# ELEKTRA-BENCH_v0_1-20240103.net
KiCad netlist of a schematic drawn in EAGLE
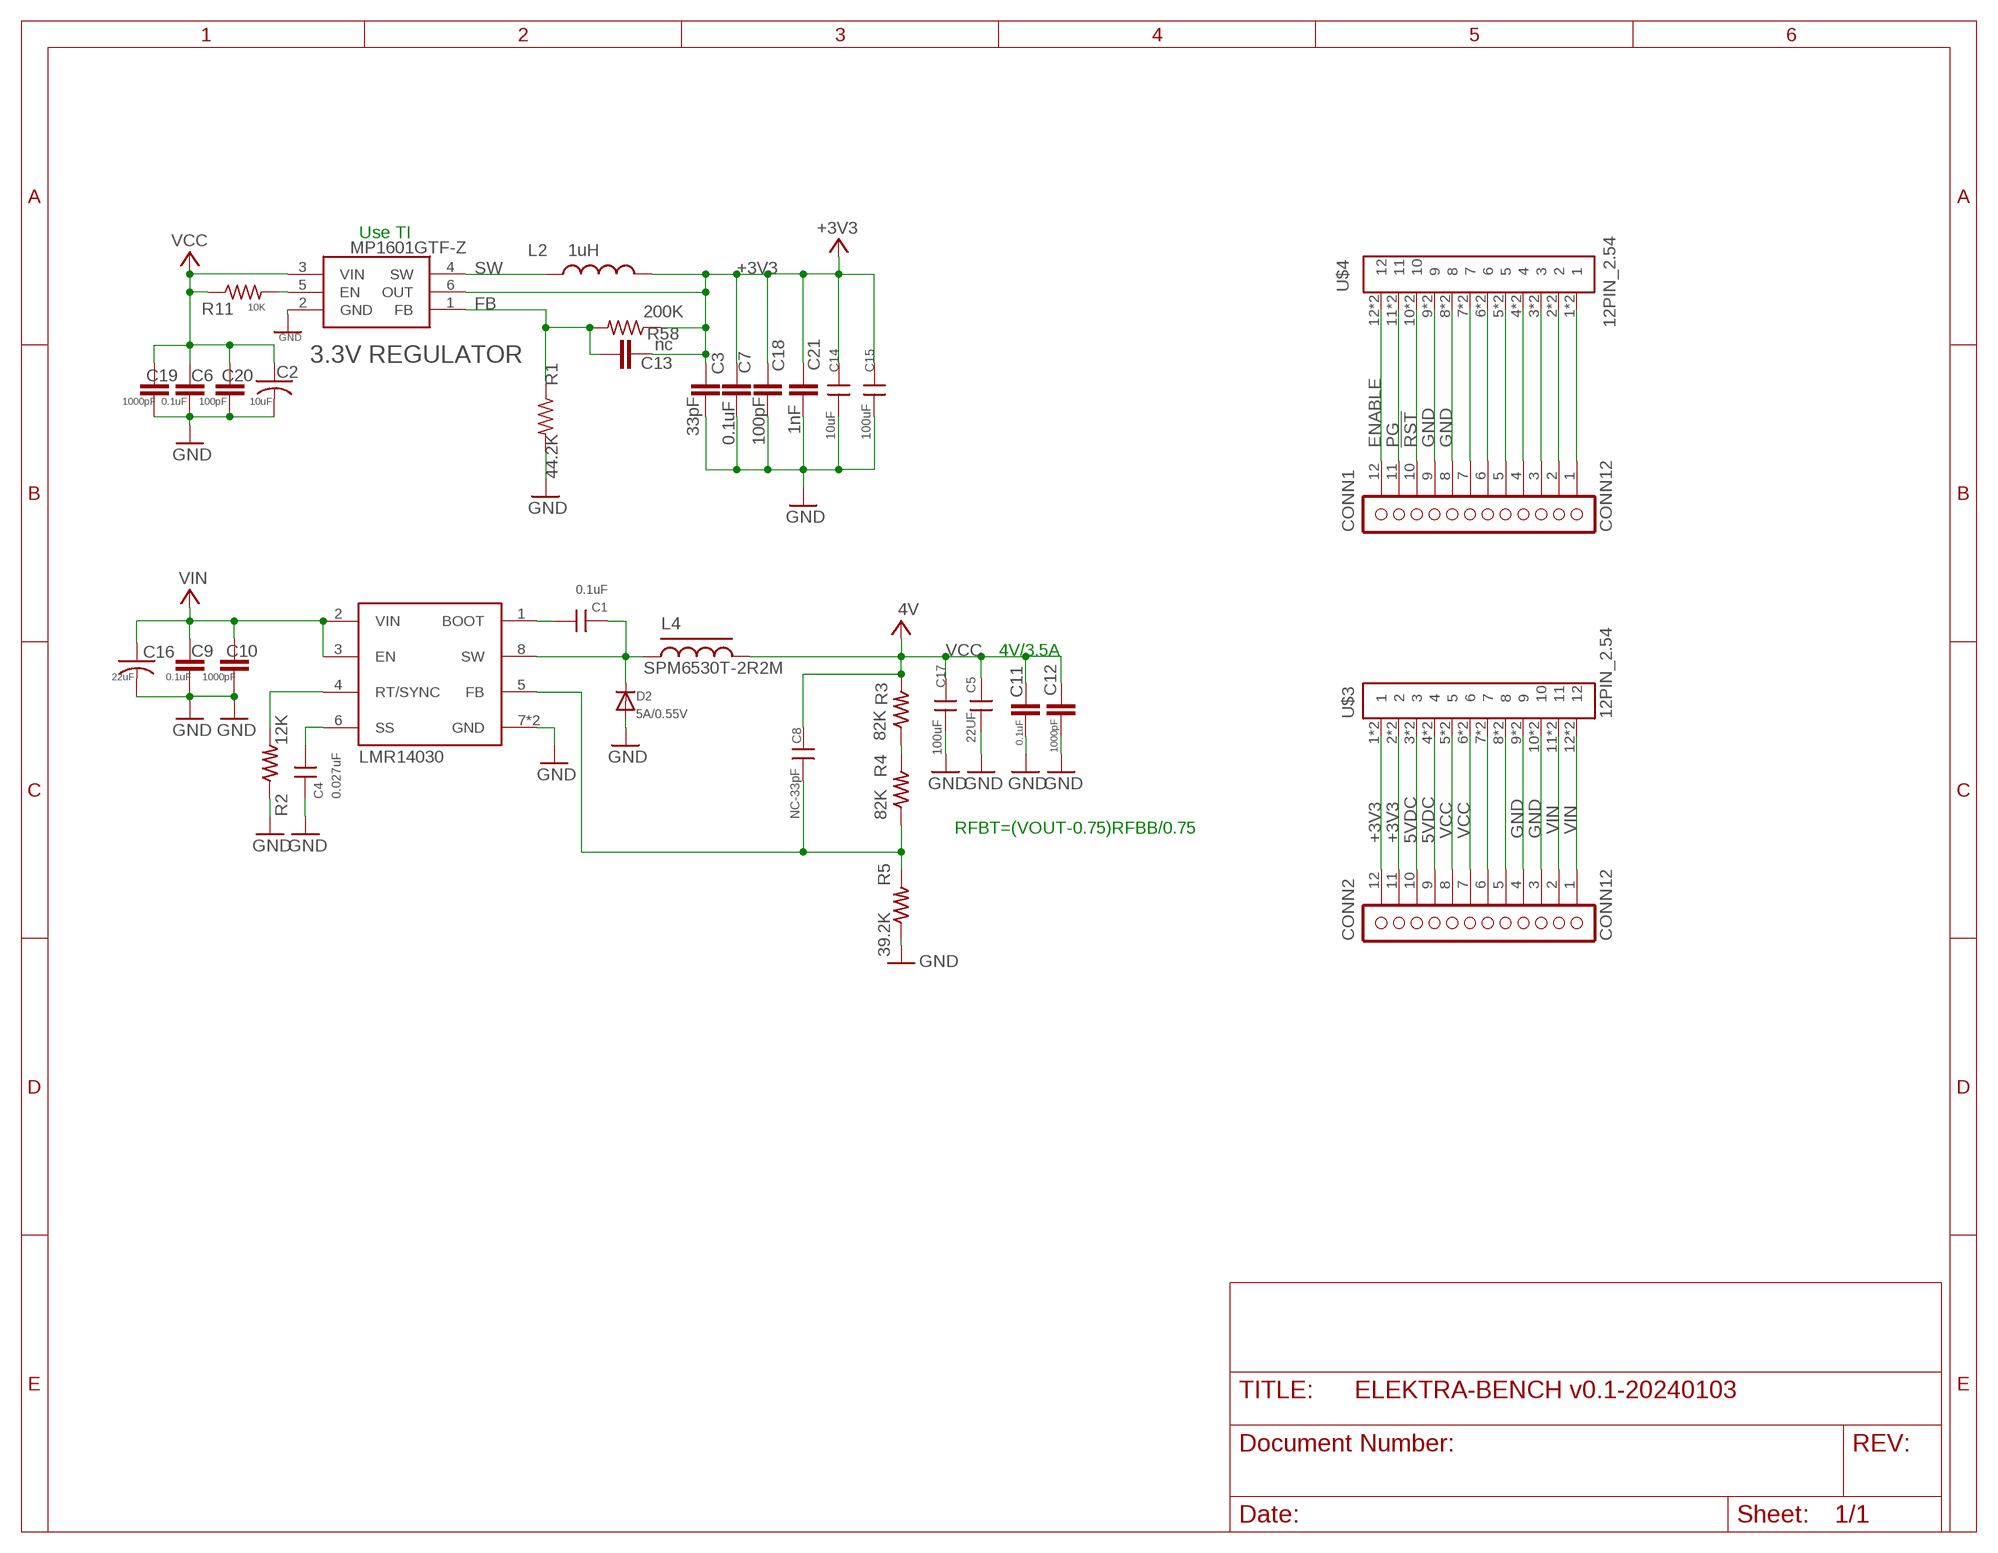
[diagram p0: schematic, sheet 1]

(export (version "E")
  (design (tool "Eeschema 10.0.6"))
  (components
    (comp (ref "C1")
      (value "0.1uF")
      (footprint "eagle-import:C0402")
      (libsource (lib "eagle-import") (part "particle SZ_21650216_CAP0402A"))
    )
    (comp (ref "C2")
      (value "10uF")
      (footprint "eagle-import:C0603_B")
      (libsource (lib "eagle-import") (part "C-US0603"))
    )
    (comp (ref "C3")
      (value "33pF")
      (footprint "eagle-import:C0402_B")
      (libsource (lib "eagle-import") (part "CAP_1"))
    )
    (comp (ref "C4")
      (value "0.027uF")
      (footprint "eagle-import:C0402")
      (libsource (lib "eagle-import") (part "particle SZ_21650216_CAP0402A"))
    )
    (comp (ref "C5")
      (value "22UF")
      (footprint "eagle-import:C0805")
      (libsource (lib "eagle-import") (part "CAPC0805"))
    )
    (comp (ref "C6")
      (value "0.1uF")
      (footprint "eagle-import:C0402_B")
      (libsource (lib "eagle-import") (part "CAP_1"))
    )
    (comp (ref "C7")
      (value "0.1uF")
      (footprint "eagle-import:C0402_B")
      (libsource (lib "eagle-import") (part "CAP_1"))
    )
    (comp (ref "C8")
      (value "NC-33pF")
      (footprint "eagle-import:C0402")
      (libsource (lib "eagle-import") (part "particle SZ_21650216_CAP0402A"))
    )
    (comp (ref "C9")
      (value "0.1uF")
      (footprint "eagle-import:C0402_B")
      (libsource (lib "eagle-import") (part "CAP_1"))
    )
    (comp (ref "C10")
      (value "1000pF")
      (footprint "eagle-import:C0402_B")
      (libsource (lib "eagle-import") (part "CAP_1"))
    )
    (comp (ref "C11")
      (value "0.1uF")
      (footprint "eagle-import:C0402_B")
      (libsource (lib "eagle-import") (part "CAP_1"))
    )
    (comp (ref "C12")
      (value "1000pF")
      (footprint "eagle-import:C0402_B")
      (libsource (lib "eagle-import") (part "CAP_1"))
    )
    (comp (ref "C13")
      (value "nc")
      (footprint "eagle-import:C0402_B")
      (libsource (lib "eagle-import") (part "CAP_1"))
    )
    (comp (ref "C14")
      (value "10uF")
      (footprint "eagle-import:C0805")
      (libsource (lib "eagle-import") (part "CAPC0805"))
    )
    (comp (ref "C15")
      (value "100uF")
      (footprint "eagle-import:C1206")
      (libsource (lib "eagle-import") (part "CAPC1206"))
    )
    (comp (ref "C16")
      (value "22uF")
      (footprint "eagle-import:C0603_B")
      (libsource (lib "eagle-import") (part "C-US0603"))
    )
    (comp (ref "C17")
      (value "100uF")
      (footprint "eagle-import:C1206")
      (libsource (lib "eagle-import") (part "CAPC1206"))
    )
    (comp (ref "C18")
      (value "100pF")
      (footprint "eagle-import:C0402_B")
      (libsource (lib "eagle-import") (part "CAP_1"))
    )
    (comp (ref "C19")
      (value "1000pF")
      (footprint "eagle-import:C0402_B")
      (libsource (lib "eagle-import") (part "CAP_1"))
    )
    (comp (ref "C20")
      (value "100pF")
      (footprint "eagle-import:C0402_B")
      (libsource (lib "eagle-import") (part "CAP_1"))
    )
    (comp (ref "C21")
      (value "1nF")
      (footprint "eagle-import:C0402_B")
      (libsource (lib "eagle-import") (part "CAP_1"))
    )
    (comp (ref "CONN1")
      (value "CONN12")
      (footprint "eagle-import:1X12_SMD_STRAIGHT")
      (libsource (lib "eagle-import") (part "CONN12"))
    )
    (comp (ref "CONN2")
      (value "CONN12")
      (footprint "eagle-import:1X12_SMD_STRAIGHT")
      (libsource (lib "eagle-import") (part "CONN12"))
    )
    (comp (ref "D2")
      (value "5A/0.55V")
      (footprint "eagle-import:SMADIODE")
      (libsource (lib "eagle-import") (part "DIODESMA"))
    )
    (comp (ref "L2")
      (value "1uH")
      (footprint "eagle-import:INDUCTOR-VLS-E")
      (libsource (lib "eagle-import") (part "INDUCTOR-SPARKFUNVLS3012ET-4R7M"))
    )
    (comp (ref "L4")
      (value "SPM6530T-2R2M")
      (footprint "eagle-import:INDCUTOR_SPM6530")
      (libsource (lib "eagle-import") (part "INDUCTOR"))
    )
    (comp (ref "R1")
      (value "44.2K")
      (footprint "eagle-import:R0402_B")
      (libsource (lib "eagle-import") (part "R-US_"))
    )
    (comp (ref "R2")
      (value "12K")
      (footprint "eagle-import:R-0402S")
      (libsource (lib "eagle-import") (part "RES0402S"))
    )
    (comp (ref "R3")
      (value "82K")
      (footprint "eagle-import:R-0402S")
      (libsource (lib "eagle-import") (part "RES0402S"))
    )
    (comp (ref "R4")
      (value "82K")
      (footprint "eagle-import:R-0402S")
      (libsource (lib "eagle-import") (part "RES0402S"))
    )
    (comp (ref "R5")
      (value "39.2K")
      (footprint "eagle-import:R-0402S")
      (libsource (lib "eagle-import") (part "RES0402S"))
    )
    (comp (ref "R11")
      (value "10K")
      (footprint "eagle-import:R0402_B")
      (libsource (lib "eagle-import") (part "Spark_R-US_"))
    )
    (comp (ref "R58")
      (value "200K")
      (footprint "eagle-import:R0402_B")
      (libsource (lib "eagle-import") (part "R-US_"))
    )
    (comp (ref "U$3")
      (value "12PIN_2.54")
      (footprint "eagle-import:12PIN_2.54")
      (libsource (lib "eagle-import") (part "12PIN_2.54"))
    )
    (comp (ref "U$4")
      (value "12PIN_2.54")
      (footprint "eagle-import:12PIN_2.54")
      (libsource (lib "eagle-import") (part "12PIN_2.54"))
    )
    (comp (ref "U2")
      (value "LMR14030")
      (footprint "eagle-import:SO_POWERPAD_8")
      (libsource (lib "eagle-import") (part "LMR14030"))
    )
    (comp (ref "U3")
      (value "MP1601GTF-Z")
      (footprint "eagle-import:SOTFL50P160X60-6N")
      (libsource (lib "eagle-import") (part "MP1601GTF-Z"))
    )
  )
  (nets
    (net (code "1") (name "+3V3") (class "Default")
      (node (ref "C13") (pin "1") (pinfunction "P$1_1") (pintype "passive"))
      (node (ref "C14") (pin "1") (pinfunction "1_1") (pintype "bidirectional"))
      (node (ref "C15") (pin "1") (pinfunction "1_1") (pintype "bidirectional"))
      (node (ref "C18") (pin "2") (pinfunction "P$2_2") (pintype "passive"))
      (node (ref "C21") (pin "2") (pinfunction "P$2_2") (pintype "passive"))
      (node (ref "C3") (pin "2") (pinfunction "P$2_2") (pintype "passive"))
      (node (ref "C7") (pin "2") (pinfunction "P$2_2") (pintype "passive"))
      (node (ref "CONN2") (pin "11") (pinfunction "11_11") (pintype "passive"))
      (node (ref "CONN2") (pin "12") (pinfunction "12_12") (pintype "passive"))
      (node (ref "L2") (pin "P$2") (pinfunction "2_P$2") (pintype "passive"))
      (node (ref "R58") (pin "1") (pinfunction "1_1") (pintype "passive"))
      (node (ref "U$3") (pin "1") (pinfunction "1_1") (pintype "bidirectional"))
      (node (ref "U$3") (pin "2") (pinfunction "2_2") (pintype "bidirectional"))
      (node (ref "U$3") (pin "P$1") (pinfunction "1_P$1") (pintype "bidirectional"))
      (node (ref "U$3") (pin "P$2") (pinfunction "2_P$2") (pintype "bidirectional"))
      (node (ref "U3") (pin "6") (pinfunction "OUT_6") (pintype "bidirectional"))
    )
    (net (code "2") (name "/5VDC") (class "Default")
      (node (ref "CONN2") (pin "10") (pinfunction "10_10") (pintype "passive"))
      (node (ref "CONN2") (pin "9") (pinfunction "9_9") (pintype "passive"))
      (node (ref "U$3") (pin "3") (pinfunction "3_3") (pintype "bidirectional"))
      (node (ref "U$3") (pin "4") (pinfunction "4_4") (pintype "bidirectional"))
      (node (ref "U$3") (pin "P$3") (pinfunction "3_P$3") (pintype "bidirectional"))
      (node (ref "U$3") (pin "P$4") (pinfunction "4_P$4") (pintype "bidirectional"))
    )
    (net (code "3") (name "/ENABLE") (class "Default")
      (node (ref "CONN1") (pin "12") (pinfunction "12_12") (pintype "passive"))
      (node (ref "U$4") (pin "12") (pinfunction "12_12") (pintype "bidirectional"))
      (node (ref "U$4") (pin "P$12") (pinfunction "12_P$12") (pintype "bidirectional"))
    )
    (net (code "4") (name "/FB") (class "Default")
      (node (ref "C13") (pin "2") (pinfunction "P$2_2") (pintype "passive"))
      (node (ref "R1") (pin "1") (pinfunction "1_1") (pintype "passive"))
      (node (ref "R58") (pin "2") (pinfunction "2_2") (pintype "passive"))
      (node (ref "U3") (pin "1") (pinfunction "FB_1") (pintype "bidirectional"))
    )
    (net (code "5") (name "/PG") (class "Default")
      (node (ref "CONN1") (pin "11") (pinfunction "11_11") (pintype "passive"))
      (node (ref "U$4") (pin "11") (pinfunction "11_11") (pintype "bidirectional"))
      (node (ref "U$4") (pin "P$11") (pinfunction "11_P$11") (pintype "bidirectional"))
    )
    (net (code "6") (name "/SW") (class "Default")
      (node (ref "L2") (pin "P$1") (pinfunction "1_P$1") (pintype "passive"))
      (node (ref "U3") (pin "4") (pinfunction "SW_4") (pintype "bidirectional"))
    )
    (net (code "7") (name "/~{RST}") (class "Default")
      (node (ref "CONN1") (pin "10") (pinfunction "10_10") (pintype "passive"))
      (node (ref "U$4") (pin "10") (pinfunction "10_10") (pintype "bidirectional"))
      (node (ref "U$4") (pin "P$10") (pinfunction "10_P$10") (pintype "bidirectional"))
    )
    (net (code "8") (name "4V") (class "Default")
      (node (ref "C11") (pin "2") (pinfunction "P$2_2") (pintype "passive"))
      (node (ref "C12") (pin "2") (pinfunction "P$2_2") (pintype "passive"))
      (node (ref "C17") (pin "1") (pinfunction "1_1") (pintype "bidirectional"))
      (node (ref "C19") (pin "2") (pinfunction "P$2_2") (pintype "passive"))
      (node (ref "C2") (pin "1") (pinfunction "1_1") (pintype "passive"))
      (node (ref "C20") (pin "2") (pinfunction "P$2_2") (pintype "passive"))
      (node (ref "C5") (pin "1") (pinfunction "1_1") (pintype "bidirectional"))
      (node (ref "C6") (pin "2") (pinfunction "P$2_2") (pintype "passive"))
      (node (ref "C8") (pin "2") (pinfunction "2_2") (pintype "bidirectional"))
      (node (ref "CONN2") (pin "7") (pinfunction "7_7") (pintype "passive"))
      (node (ref "CONN2") (pin "8") (pinfunction "8_8") (pintype "passive"))
      (node (ref "L4") (pin "2") (pinfunction "2_2") (pintype "bidirectional"))
      (node (ref "R11") (pin "1") (pinfunction "1_1") (pintype "passive"))
      (node (ref "R3") (pin "2") (pinfunction "2_2") (pintype "bidirectional"))
      (node (ref "U$3") (pin "5") (pinfunction "5_5") (pintype "bidirectional"))
      (node (ref "U$3") (pin "6") (pinfunction "6_6") (pintype "bidirectional"))
      (node (ref "U$3") (pin "P$5") (pinfunction "5_P$5") (pintype "bidirectional"))
      (node (ref "U$3") (pin "P$6") (pinfunction "6_P$6") (pintype "bidirectional"))
      (node (ref "U3") (pin "3") (pinfunction "VIN_3") (pintype "bidirectional"))
    )
    (net (code "9") (name "GND") (class "Default")
      (node (ref "C10") (pin "1") (pinfunction "P$1_1") (pintype "passive"))
      (node (ref "C11") (pin "1") (pinfunction "P$1_1") (pintype "passive"))
      (node (ref "C12") (pin "1") (pinfunction "P$1_1") (pintype "passive"))
      (node (ref "C14") (pin "2") (pinfunction "2_2") (pintype "bidirectional"))
      (node (ref "C15") (pin "2") (pinfunction "2_2") (pintype "bidirectional"))
      (node (ref "C16") (pin "2") (pinfunction "2_2") (pintype "passive"))
      (node (ref "C17") (pin "2") (pinfunction "2_2") (pintype "bidirectional"))
      (node (ref "C18") (pin "1") (pinfunction "P$1_1") (pintype "passive"))
      (node (ref "C19") (pin "1") (pinfunction "P$1_1") (pintype "passive"))
      (node (ref "C2") (pin "2") (pinfunction "2_2") (pintype "passive"))
      (node (ref "C20") (pin "1") (pinfunction "P$1_1") (pintype "passive"))
      (node (ref "C21") (pin "1") (pinfunction "P$1_1") (pintype "passive"))
      (node (ref "C3") (pin "1") (pinfunction "P$1_1") (pintype "passive"))
      (node (ref "C4") (pin "2") (pinfunction "2_2") (pintype "bidirectional"))
      (node (ref "C5") (pin "2") (pinfunction "2_2") (pintype "bidirectional"))
      (node (ref "C6") (pin "1") (pinfunction "P$1_1") (pintype "passive"))
      (node (ref "C7") (pin "1") (pinfunction "P$1_1") (pintype "passive"))
      (node (ref "C9") (pin "1") (pinfunction "P$1_1") (pintype "passive"))
      (node (ref "CONN1") (pin "8") (pinfunction "8_8") (pintype "passive"))
      (node (ref "CONN1") (pin "9") (pinfunction "9_9") (pintype "passive"))
      (node (ref "CONN2") (pin "3") (pinfunction "3_3") (pintype "passive"))
      (node (ref "CONN2") (pin "4") (pinfunction "4_4") (pintype "passive"))
      (node (ref "D2") (pin "A") (pinfunction "A_A") (pintype "passive"))
      (node (ref "R1") (pin "2") (pinfunction "2_2") (pintype "passive"))
      (node (ref "R2") (pin "1") (pinfunction "1_1") (pintype "bidirectional"))
      (node (ref "R5") (pin "1") (pinfunction "1_1") (pintype "bidirectional"))
      (node (ref "U$3") (pin "10") (pinfunction "10_10") (pintype "bidirectional"))
      (node (ref "U$3") (pin "9") (pinfunction "9_9") (pintype "bidirectional"))
      (node (ref "U$3") (pin "P$10") (pinfunction "10_P$10") (pintype "bidirectional"))
      (node (ref "U$3") (pin "P$9") (pinfunction "9_P$9") (pintype "bidirectional"))
      (node (ref "U$4") (pin "8") (pinfunction "8_8") (pintype "bidirectional"))
      (node (ref "U$4") (pin "9") (pinfunction "9_9") (pintype "bidirectional"))
      (node (ref "U$4") (pin "P$8") (pinfunction "8_P$8") (pintype "bidirectional"))
      (node (ref "U$4") (pin "P$9") (pinfunction "9_P$9") (pintype "bidirectional"))
      (node (ref "U2") (pin "7") (pinfunction "GND_7") (pintype "bidirectional"))
      (node (ref "U2") (pin "EP") (pinfunction "GND_EP") (pintype "bidirectional"))
      (node (ref "U3") (pin "2") (pinfunction "GND_2") (pintype "bidirectional"))
    )
    (net (code "10") (name "Net-(CONN1-Pad1)") (class "Default")
      (node (ref "CONN1") (pin "1") (pinfunction "1_1") (pintype "passive"))
      (node (ref "U$4") (pin "1") (pinfunction "1_1") (pintype "bidirectional"))
      (node (ref "U$4") (pin "P$1") (pinfunction "1_P$1") (pintype "bidirectional"))
    )
    (net (code "11") (name "Net-(CONN1-Pad2)") (class "Default")
      (node (ref "CONN1") (pin "2") (pinfunction "2_2") (pintype "passive"))
      (node (ref "U$4") (pin "2") (pinfunction "2_2") (pintype "bidirectional"))
      (node (ref "U$4") (pin "P$2") (pinfunction "2_P$2") (pintype "bidirectional"))
    )
    (net (code "12") (name "Net-(CONN1-Pad3)") (class "Default")
      (node (ref "CONN1") (pin "3") (pinfunction "3_3") (pintype "passive"))
      (node (ref "U$4") (pin "3") (pinfunction "3_3") (pintype "bidirectional"))
      (node (ref "U$4") (pin "P$3") (pinfunction "3_P$3") (pintype "bidirectional"))
    )
    (net (code "13") (name "Net-(CONN1-Pad4)") (class "Default")
      (node (ref "CONN1") (pin "4") (pinfunction "4_4") (pintype "passive"))
      (node (ref "U$4") (pin "4") (pinfunction "4_4") (pintype "bidirectional"))
      (node (ref "U$4") (pin "P$4") (pinfunction "4_P$4") (pintype "bidirectional"))
    )
    (net (code "14") (name "Net-(CONN1-Pad5)") (class "Default")
      (node (ref "CONN1") (pin "5") (pinfunction "5_5") (pintype "passive"))
      (node (ref "U$4") (pin "5") (pinfunction "5_5") (pintype "bidirectional"))
      (node (ref "U$4") (pin "P$5") (pinfunction "5_P$5") (pintype "bidirectional"))
    )
    (net (code "15") (name "Net-(CONN1-Pad6)") (class "Default")
      (node (ref "CONN1") (pin "6") (pinfunction "6_6") (pintype "passive"))
      (node (ref "U$4") (pin "6") (pinfunction "6_6") (pintype "bidirectional"))
      (node (ref "U$4") (pin "P$6") (pinfunction "6_P$6") (pintype "bidirectional"))
    )
    (net (code "16") (name "Net-(CONN1-Pad7)") (class "Default")
      (node (ref "CONN1") (pin "7") (pinfunction "7_7") (pintype "passive"))
      (node (ref "U$4") (pin "7") (pinfunction "7_7") (pintype "bidirectional"))
      (node (ref "U$4") (pin "P$7") (pinfunction "7_P$7") (pintype "bidirectional"))
    )
    (net (code "17") (name "Net-(CONN2-Pad5)") (class "Default")
      (node (ref "CONN2") (pin "5") (pinfunction "5_5") (pintype "passive"))
      (node (ref "U$3") (pin "8") (pinfunction "8_8") (pintype "bidirectional"))
      (node (ref "U$3") (pin "P$8") (pinfunction "8_P$8") (pintype "bidirectional"))
    )
    (net (code "18") (name "Net-(CONN2-Pad6)") (class "Default")
      (node (ref "CONN2") (pin "6") (pinfunction "6_6") (pintype "passive"))
      (node (ref "U$3") (pin "7") (pinfunction "7_7") (pintype "bidirectional"))
      (node (ref "U$3") (pin "P$7") (pinfunction "7_P$7") (pintype "bidirectional"))
    )
    (net (code "19") (name "Net-(R3-Pad1)") (class "Default")
      (node (ref "R3") (pin "1") (pinfunction "1_1") (pintype "bidirectional"))
      (node (ref "R4") (pin "2") (pinfunction "2_2") (pintype "bidirectional"))
    )
    (net (code "20") (name "Net-(U2-BOOT)") (class "Default")
      (node (ref "C1") (pin "1") (pinfunction "1_1") (pintype "bidirectional"))
      (node (ref "U2") (pin "1") (pinfunction "BOOT_1") (pintype "bidirectional"))
    )
    (net (code "21") (name "Net-(U2-FB)") (class "Default")
      (node (ref "C8") (pin "1") (pinfunction "1_1") (pintype "bidirectional"))
      (node (ref "R4") (pin "1") (pinfunction "1_1") (pintype "bidirectional"))
      (node (ref "R5") (pin "2") (pinfunction "2_2") (pintype "bidirectional"))
      (node (ref "U2") (pin "5") (pinfunction "FB_5") (pintype "bidirectional"))
    )
    (net (code "22") (name "Net-(U2-RT{slash}SYNC)") (class "Default")
      (node (ref "R2") (pin "2") (pinfunction "2_2") (pintype "bidirectional"))
      (node (ref "U2") (pin "4") (pinfunction "RT/SYNC_4") (pintype "bidirectional"))
    )
    (net (code "23") (name "Net-(U2-SS)") (class "Default")
      (node (ref "C4") (pin "1") (pinfunction "1_1") (pintype "bidirectional"))
      (node (ref "U2") (pin "6") (pinfunction "SS_6") (pintype "bidirectional"))
    )
    (net (code "24") (name "Net-(U2-SW)") (class "Default")
      (node (ref "C1") (pin "2") (pinfunction "2_2") (pintype "bidirectional"))
      (node (ref "D2") (pin "C") (pinfunction "C_C") (pintype "passive"))
      (node (ref "L4") (pin "1") (pinfunction "1_1") (pintype "bidirectional"))
      (node (ref "U2") (pin "8") (pinfunction "SW_8") (pintype "bidirectional"))
    )
    (net (code "25") (name "Net-(U3-EN)") (class "Default")
      (node (ref "R11") (pin "2") (pinfunction "2_2") (pintype "passive"))
      (node (ref "U3") (pin "5") (pinfunction "EN_5") (pintype "bidirectional"))
    )
    (net (code "26") (name "VIN") (class "Default")
      (node (ref "C10") (pin "2") (pinfunction "P$2_2") (pintype "passive"))
      (node (ref "C16") (pin "1") (pinfunction "1_1") (pintype "passive"))
      (node (ref "C9") (pin "2") (pinfunction "P$2_2") (pintype "passive"))
      (node (ref "CONN2") (pin "1") (pinfunction "1_1") (pintype "passive"))
      (node (ref "CONN2") (pin "2") (pinfunction "2_2") (pintype "passive"))
      (node (ref "U$3") (pin "11") (pinfunction "11_11") (pintype "bidirectional"))
      (node (ref "U$3") (pin "12") (pinfunction "12_12") (pintype "bidirectional"))
      (node (ref "U$3") (pin "P$11") (pinfunction "11_P$11") (pintype "bidirectional"))
      (node (ref "U$3") (pin "P$12") (pinfunction "12_P$12") (pintype "bidirectional"))
      (node (ref "U2") (pin "2") (pinfunction "VIN_2") (pintype "bidirectional"))
      (node (ref "U2") (pin "3") (pinfunction "EN_3") (pintype "bidirectional"))
    )
  )
)
